# voltage_adj_current_source.net
KiCad netlist of a schematic drawn in Altium Designer
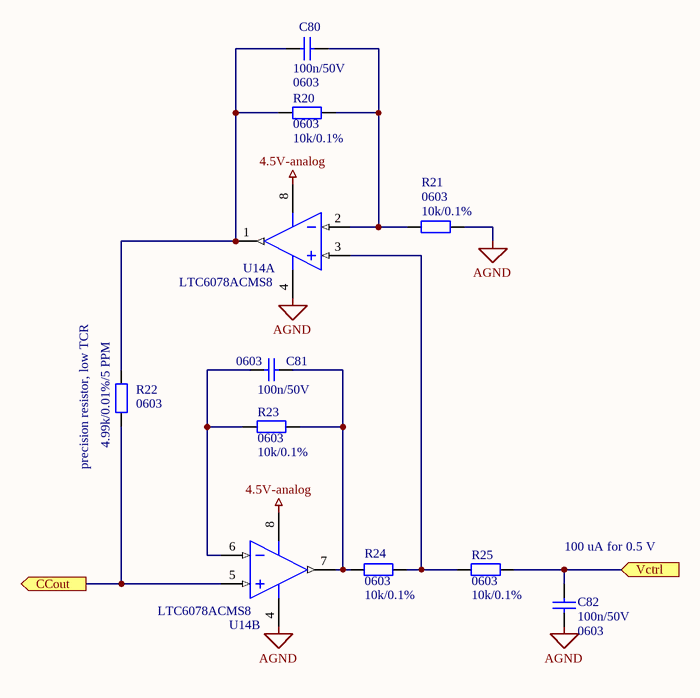
[diagram p0: voltage_adj_current_source.SchDoc]

(export (version "E")
  (design (tool "Eeschema 10.0.6"))
  (components
    (comp (ref "C80")
      (value "100n/50V")
      (footprint "SMD_Capacitor_0603")
      (description "Ceramic Cap Kemet COTS 100n/50V X7R 0603")
      (fields
        (field (name "MANUFACTURER") "Kemet")
        (field (name "MANUFACTURERPARTNUMBER") "C0603T104K5RALTU")
        (field (name "PACKAGE") "0603")
      )
      (libsource (lib "capacitors") (part "Cer_C0603T104K5RALTU"))
    )
    (comp (ref "C81")
      (value "100n/50V")
      (footprint "SMD_Capacitor_0603")
      (description "Ceramic Cap Kemet COTS 100n/50V X7R 0603")
      (fields
        (field (name "MANUFACTURER") "Kemet")
        (field (name "MANUFACTURERPARTNUMBER") "C0603T104K5RALTU")
        (field (name "PACKAGE") "0603")
      )
      (libsource (lib "capacitors") (part "Cer_C0603T104K5RALTU"))
    )
    (comp (ref "C82")
      (value "100n/50V")
      (footprint "SMD_Capacitor_0603")
      (description "Ceramic Cap Kemet COTS 100n/50V X7R 0603")
      (fields
        (field (name "MANUFACTURER") "Kemet")
        (field (name "MANUFACTURERPARTNUMBER") "C0603T104K5RALTU")
        (field (name "PACKAGE") "0603")
      )
      (libsource (lib "capacitors") (part "Cer_C0603T104K5RALTU"))
    )
    (comp (ref "R20")
      (value "0603")
      (footprint "SMD_Resistor_0603")
      (description "Resistor")
      (fields (field (name "ALTIUM_VALUE") "10k/0.1%") (field (name "PUBLISHER") "Altium Limited"))
      (libsource (lib "Miscellaneous Devices") (part "Res2"))
    )
    (comp (ref "R21")
      (value "0603")
      (footprint "SMD_Resistor_0603")
      (description "Resistor")
      (fields (field (name "ALTIUM_VALUE") "10k/0.1%") (field (name "PUBLISHER") "Altium Limited"))
      (libsource (lib "Miscellaneous Devices") (part "Res2"))
    )
    (comp (ref "R22")
      (value "0603")
      (footprint "SMD_Resistor_0603")
      (description "Resistor")
      (fields (field (name "ALTIUM_VALUE") "4.99k/0.01%/5 PPM") (field (name "PUBLISHER") "Altium Limited"))
      (libsource (lib "") (part "Res2_1"))
    )
    (comp (ref "R23")
      (value "0603")
      (footprint "SMD_Resistor_0603")
      (description "Resistor")
      (fields (field (name "ALTIUM_VALUE") "10k/0.1%") (field (name "PUBLISHER") "Altium Limited"))
      (libsource (lib "Miscellaneous Devices") (part "Res2"))
    )
    (comp (ref "R24")
      (value "0603")
      (footprint "SMD_Resistor_0603")
      (description "Resistor")
      (fields (field (name "ALTIUM_VALUE") "10k/0.1%") (field (name "PUBLISHER") "Altium Limited"))
      (libsource (lib "Miscellaneous Devices") (part "Res2"))
    )
    (comp (ref "R25")
      (value "0603")
      (footprint "SMD_Resistor_0603")
      (description "Resistor")
      (fields (field (name "ALTIUM_VALUE") "10k/0.1%") (field (name "PUBLISHER") "Altium Limited"))
      (libsource (lib "Miscellaneous Devices") (part "Res2"))
    )
    (comp (ref "U14")
      (value "LTC6078ACMS8")
      (footprint "LT-MS8-8_N")
      (fields
        (field (name "LINEAR TECHNOLOGY PART NUMBER") "LTC6078")
        (field (name "MANUFACTURER") "Linear Technology")
      )
      (libsource (lib "Linear Technology Operational Amplifiers (LT2000-LT6000)") (part "LTC6078ACMS8"))
    )
  )
  (nets
    (net (code "1") (name "/CCout") (class "Default")
      (node (ref "R22") (pin "1") (pinfunction "1_1") (pintype "passive"))
      (node (ref "U14") (pin "5") (pinfunction "+INB_5") (pintype "input"))
    )
    (net (code "2") (name "/Vctrl") (class "Default")
      (node (ref "C82") (pin "2") (pinfunction "2_2") (pintype "passive"))
      (node (ref "R25") (pin "1") (pinfunction "1_1") (pintype "passive"))
    )
    (net (code "3") (name "4.5V-analog") (class "Default")
      (node (ref "U14") (pin "8") (pinfunction "V+_8") (pintype "power_in"))
    )
    (net (code "4") (name "AGND") (class "Default")
      (node (ref "C82") (pin "1") (pinfunction "1_1") (pintype "passive"))
      (node (ref "R21") (pin "1") (pinfunction "1_1") (pintype "passive"))
      (node (ref "U14") (pin "4") (pinfunction "V-_4") (pintype "power_in"))
    )
    (net (code "5") (name "Net-(U14A-+INA)") (class "Default")
      (node (ref "R24") (pin "1") (pinfunction "1_1") (pintype "passive"))
      (node (ref "R25") (pin "2") (pinfunction "2_2") (pintype "passive"))
      (node (ref "U14") (pin "3") (pinfunction "+INA_3") (pintype "input"))
    )
    (net (code "6") (name "Net-(U14A--INA)") (class "Default")
      (node (ref "C80") (pin "2") (pinfunction "2_2") (pintype "passive"))
      (node (ref "R20") (pin "1") (pinfunction "1_1") (pintype "passive"))
      (node (ref "R21") (pin "2") (pinfunction "2_2") (pintype "passive"))
      (node (ref "U14") (pin "2") (pinfunction "-INA_2") (pintype "input"))
    )
    (net (code "7") (name "Net-(U14A-OUTA)") (class "Default")
      (node (ref "C80") (pin "1") (pinfunction "1_1") (pintype "passive"))
      (node (ref "R20") (pin "2") (pinfunction "2_2") (pintype "passive"))
      (node (ref "R22") (pin "2") (pinfunction "2_2") (pintype "passive"))
      (node (ref "U14") (pin "1") (pinfunction "OUTA_1") (pintype "output"))
    )
    (net (code "8") (name "Net-(U14B--INB)") (class "Default")
      (node (ref "C81") (pin "1") (pinfunction "1_1") (pintype "passive"))
      (node (ref "R23") (pin "2") (pinfunction "2_2") (pintype "passive"))
      (node (ref "U14") (pin "6") (pinfunction "-INB_6") (pintype "input"))
    )
    (net (code "9") (name "Net-(U14B-OUTB)") (class "Default")
      (node (ref "C81") (pin "2") (pinfunction "2_2") (pintype "passive"))
      (node (ref "R23") (pin "1") (pinfunction "1_1") (pintype "passive"))
      (node (ref "R24") (pin "2") (pinfunction "2_2") (pintype "passive"))
      (node (ref "U14") (pin "7") (pinfunction "OUTB_7") (pintype "output"))
    )
  )
)
